# 08_-_QSFP28_2.net
KiCad netlist of a schematic drawn in Altium Designer
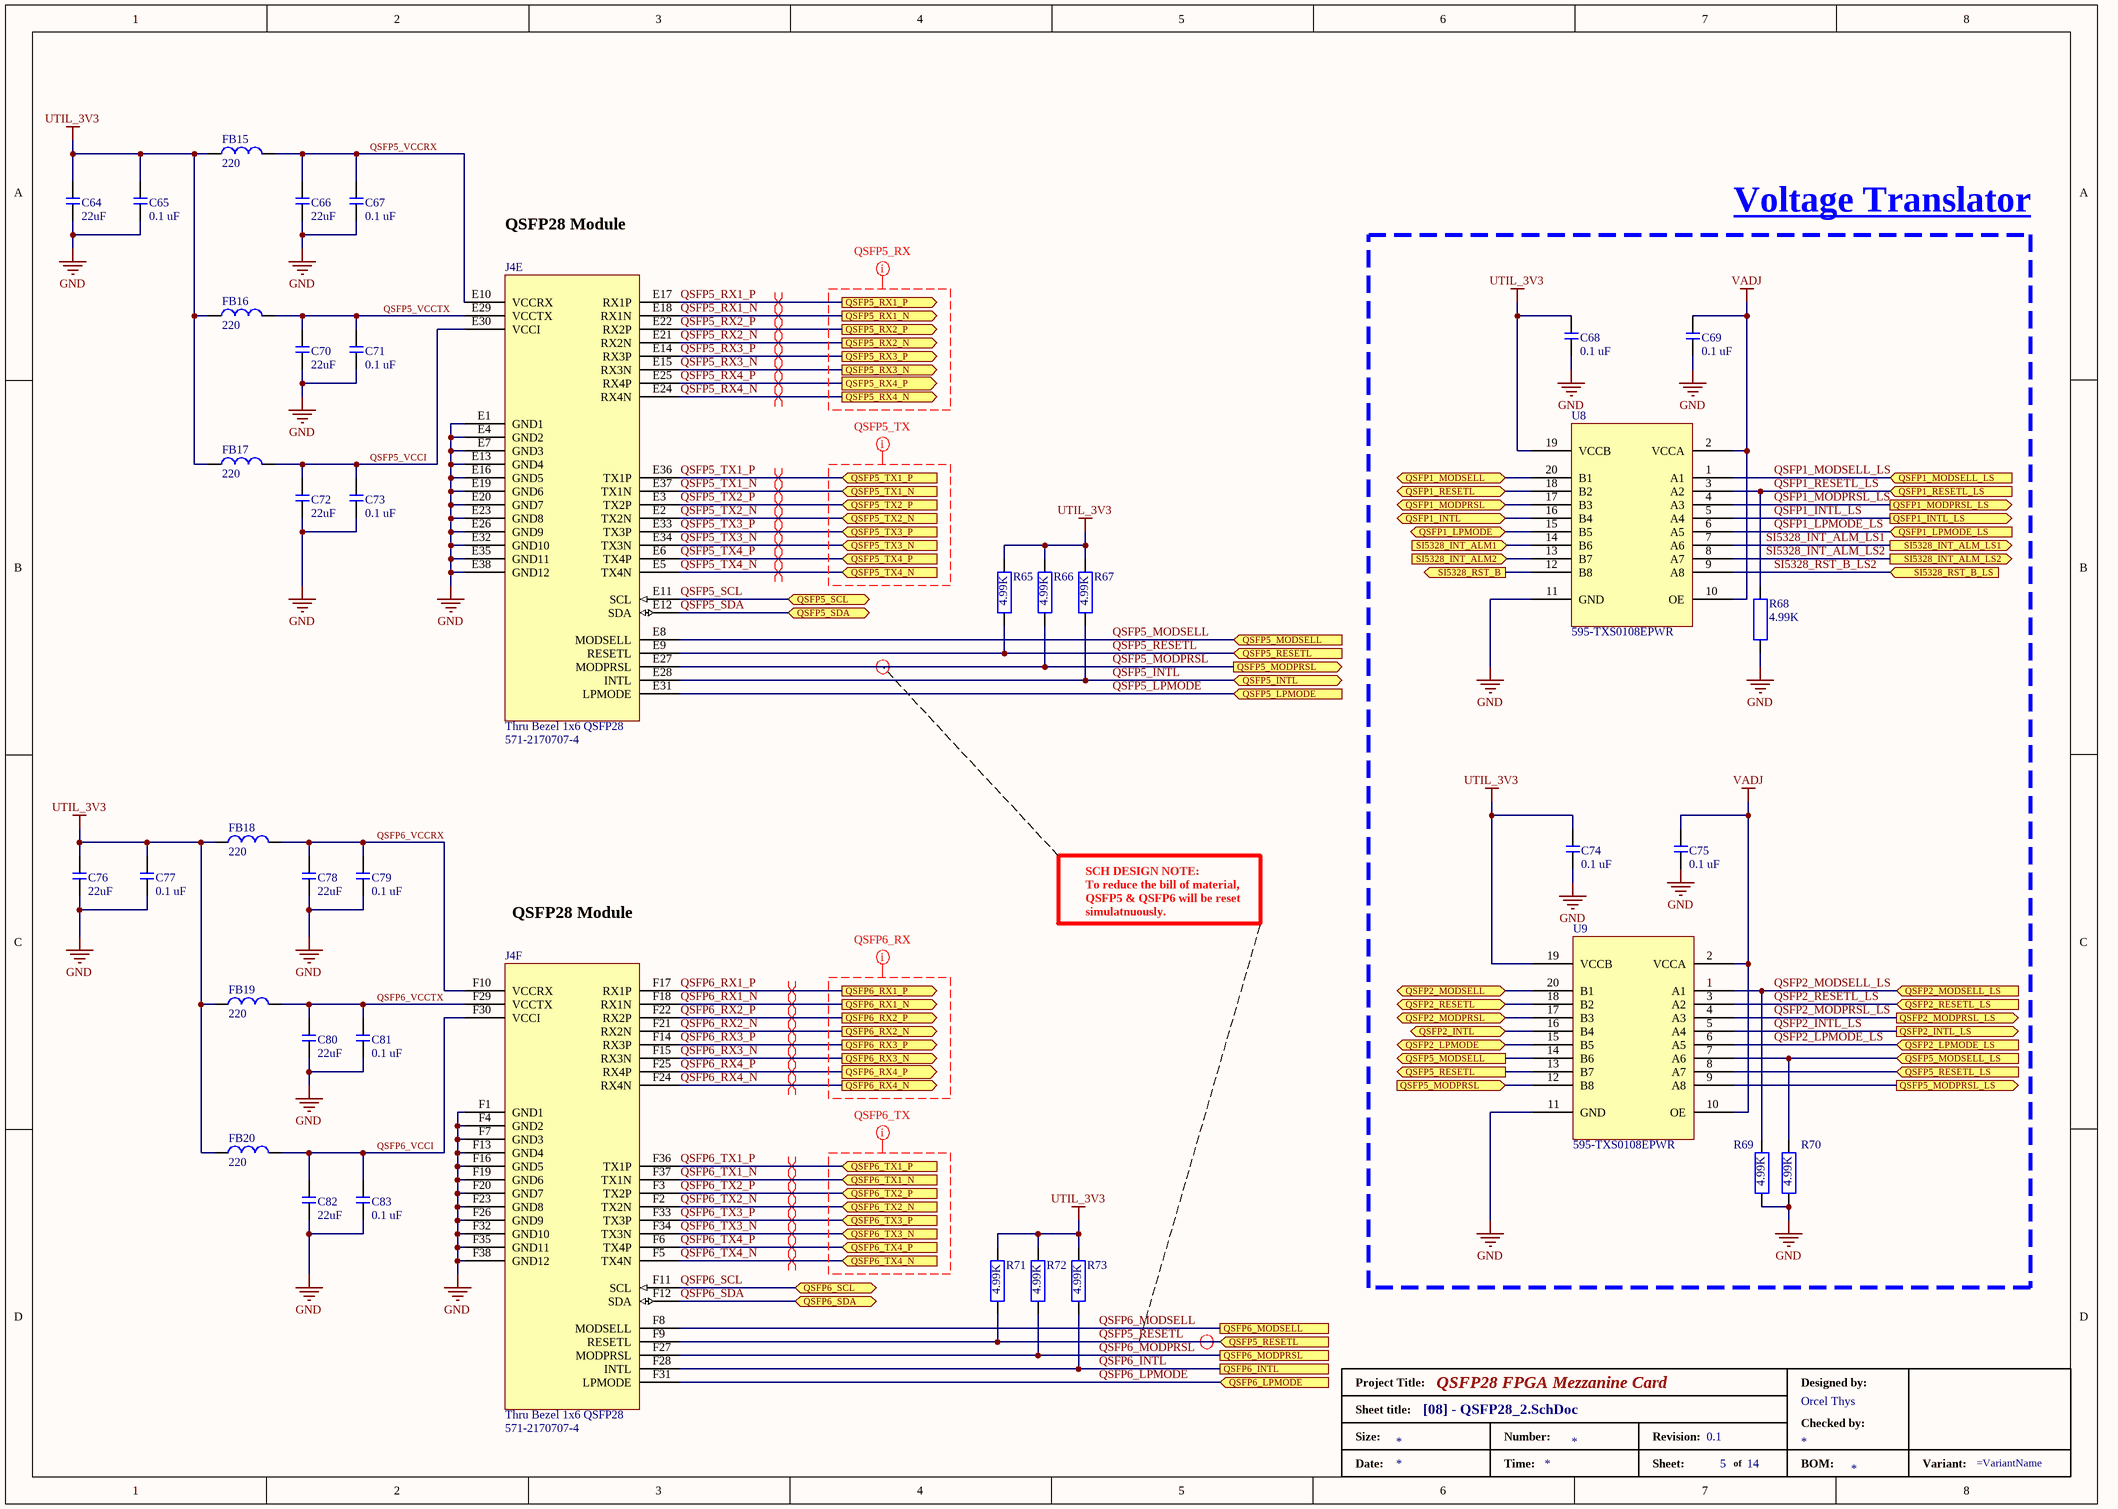
[diagram p0: [08] - QSFP28_2.SchDoc]

(export (version "E")
  (design (tool "Eeschema 10.0.6"))
  (components
    (comp (ref "C64")
      (value "22uF")
      (footprint "C2012")
      (description "Cap Series 0805 22 uF 35 V ±20 % Tolerance X5R SMT Multilayer Ceramic Capacitor")
      (fields
        (field (name "MANUFACTURER") "TDK")
        (field (name "MANUFACTURER PART NUMBER") "C2012X5R1V226M125AC")
      )
      (libsource (lib "QSFP28_FMC_lib") (part "C2012X5R1V226M125AC"))
    )
    (comp (ref "C65")
      (value "0.1 uF")
      (footprint "C0402")
      (description "Cap 0402 0.1 uF 50 V ±10 % Tolerance X7R Surface Mount Multilayer Ceramic Capacitor")
      (fields
        (field (name "MANUFACTURER") "Taiyo Yuden")
        (field (name "MANUFACTURER PART NUMBER") "UMK105B7104KV-FR")
      )
      (libsource (lib "QSFP28_FMC_lib") (part "UMK105B7104KV-FR"))
    )
    (comp (ref "C66")
      (value "22uF")
      (footprint "C2012")
      (description "Cap Series 0805 22 uF 35 V ±20 % Tolerance X5R SMT Multilayer Ceramic Capacitor")
      (fields
        (field (name "MANUFACTURER") "TDK")
        (field (name "MANUFACTURER PART NUMBER") "C2012X5R1V226M125AC")
      )
      (libsource (lib "QSFP28_FMC_lib") (part "C2012X5R1V226M125AC"))
    )
    (comp (ref "C67")
      (value "0.1 uF")
      (footprint "C0402")
      (description "Cap 0402 0.1 uF 50 V ±10 % Tolerance X7R Surface Mount Multilayer Ceramic Capacitor")
      (fields
        (field (name "MANUFACTURER") "Taiyo Yuden")
        (field (name "MANUFACTURER PART NUMBER") "UMK105B7104KV-FR")
      )
      (libsource (lib "QSFP28_FMC_lib") (part "UMK105B7104KV-FR"))
    )
    (comp (ref "C68")
      (value "0.1 uF")
      (footprint "C0402")
      (description "Cap 0402 0.1 uF 50 V ±10 % Tolerance X7R Surface Mount Multilayer Ceramic Capacitor")
      (fields
        (field (name "MANUFACTURER") "Taiyo Yuden")
        (field (name "MANUFACTURER PART NUMBER") "UMK105B7104KV-FR")
      )
      (libsource (lib "QSFP28_FMC_lib") (part "UMK105B7104KV-FR"))
    )
    (comp (ref "C69")
      (value "0.1 uF")
      (footprint "C0402")
      (description "Cap 0402 0.1 uF 50 V ±10 % Tolerance X7R Surface Mount Multilayer Ceramic Capacitor")
      (fields
        (field (name "MANUFACTURER") "Taiyo Yuden")
        (field (name "MANUFACTURER PART NUMBER") "UMK105B7104KV-FR")
      )
      (libsource (lib "QSFP28_FMC_lib") (part "UMK105B7104KV-FR"))
    )
    (comp (ref "C70")
      (value "22uF")
      (footprint "C2012")
      (description "Cap Series 0805 22 uF 35 V ±20 % Tolerance X5R SMT Multilayer Ceramic Capacitor")
      (fields
        (field (name "MANUFACTURER") "TDK")
        (field (name "MANUFACTURER PART NUMBER") "C2012X5R1V226M125AC")
      )
      (libsource (lib "QSFP28_FMC_lib") (part "C2012X5R1V226M125AC"))
    )
    (comp (ref "C71")
      (value "0.1 uF")
      (footprint "C0402")
      (description "Cap 0402 0.1 uF 50 V ±10 % Tolerance X7R Surface Mount Multilayer Ceramic Capacitor")
      (fields
        (field (name "MANUFACTURER") "Taiyo Yuden")
        (field (name "MANUFACTURER PART NUMBER") "UMK105B7104KV-FR")
      )
      (libsource (lib "QSFP28_FMC_lib") (part "UMK105B7104KV-FR"))
    )
    (comp (ref "C72")
      (value "22uF")
      (footprint "C2012")
      (description "Cap Series 0805 22 uF 35 V ±20 % Tolerance X5R SMT Multilayer Ceramic Capacitor")
      (fields
        (field (name "MANUFACTURER") "TDK")
        (field (name "MANUFACTURER PART NUMBER") "C2012X5R1V226M125AC")
      )
      (libsource (lib "QSFP28_FMC_lib") (part "C2012X5R1V226M125AC"))
    )
    (comp (ref "C73")
      (value "0.1 uF")
      (footprint "C0402")
      (description "Cap 0402 0.1 uF 50 V ±10 % Tolerance X7R Surface Mount Multilayer Ceramic Capacitor")
      (fields
        (field (name "MANUFACTURER") "Taiyo Yuden")
        (field (name "MANUFACTURER PART NUMBER") "UMK105B7104KV-FR")
      )
      (libsource (lib "QSFP28_FMC_lib") (part "UMK105B7104KV-FR"))
    )
    (comp (ref "C74")
      (value "0.1 uF")
      (footprint "C0402")
      (description "Cap 0402 0.1 uF 50 V ±10 % Tolerance X7R Surface Mount Multilayer Ceramic Capacitor")
      (fields
        (field (name "MANUFACTURER") "Taiyo Yuden")
        (field (name "MANUFACTURER PART NUMBER") "UMK105B7104KV-FR")
      )
      (libsource (lib "QSFP28_FMC_lib") (part "UMK105B7104KV-FR"))
    )
    (comp (ref "C75")
      (value "0.1 uF")
      (footprint "C0402")
      (description "Cap 0402 0.1 uF 50 V ±10 % Tolerance X7R Surface Mount Multilayer Ceramic Capacitor")
      (fields
        (field (name "MANUFACTURER") "Taiyo Yuden")
        (field (name "MANUFACTURER PART NUMBER") "UMK105B7104KV-FR")
      )
      (libsource (lib "QSFP28_FMC_lib") (part "UMK105B7104KV-FR"))
    )
    (comp (ref "C76")
      (value "22uF")
      (footprint "C2012")
      (description "Cap Series 0805 22 uF 35 V ±20 % Tolerance X5R SMT Multilayer Ceramic Capacitor")
      (fields
        (field (name "MANUFACTURER") "TDK")
        (field (name "MANUFACTURER PART NUMBER") "C2012X5R1V226M125AC")
      )
      (libsource (lib "QSFP28_FMC_lib") (part "C2012X5R1V226M125AC"))
    )
    (comp (ref "C77")
      (value "0.1 uF")
      (footprint "C0402")
      (description "Cap 0402 0.1 uF 50 V ±10 % Tolerance X7R Surface Mount Multilayer Ceramic Capacitor")
      (fields
        (field (name "MANUFACTURER") "Taiyo Yuden")
        (field (name "MANUFACTURER PART NUMBER") "UMK105B7104KV-FR")
      )
      (libsource (lib "QSFP28_FMC_lib") (part "UMK105B7104KV-FR"))
    )
    (comp (ref "C78")
      (value "22uF")
      (footprint "C2012")
      (description "Cap Series 0805 22 uF 35 V ±20 % Tolerance X5R SMT Multilayer Ceramic Capacitor")
      (fields
        (field (name "MANUFACTURER") "TDK")
        (field (name "MANUFACTURER PART NUMBER") "C2012X5R1V226M125AC")
      )
      (libsource (lib "QSFP28_FMC_lib") (part "C2012X5R1V226M125AC"))
    )
    (comp (ref "C79")
      (value "0.1 uF")
      (footprint "C0402")
      (description "Cap 0402 0.1 uF 50 V ±10 % Tolerance X7R Surface Mount Multilayer Ceramic Capacitor")
      (fields
        (field (name "MANUFACTURER") "Taiyo Yuden")
        (field (name "MANUFACTURER PART NUMBER") "UMK105B7104KV-FR")
      )
      (libsource (lib "QSFP28_FMC_lib") (part "UMK105B7104KV-FR"))
    )
    (comp (ref "C80")
      (value "22uF")
      (footprint "C2012")
      (description "Cap Series 0805 22 uF 35 V ±20 % Tolerance X5R SMT Multilayer Ceramic Capacitor")
      (fields
        (field (name "MANUFACTURER") "TDK")
        (field (name "MANUFACTURER PART NUMBER") "C2012X5R1V226M125AC")
      )
      (libsource (lib "QSFP28_FMC_lib") (part "C2012X5R1V226M125AC"))
    )
    (comp (ref "C81")
      (value "0.1 uF")
      (footprint "C0402")
      (description "Cap 0402 0.1 uF 50 V ±10 % Tolerance X7R Surface Mount Multilayer Ceramic Capacitor")
      (fields
        (field (name "MANUFACTURER") "Taiyo Yuden")
        (field (name "MANUFACTURER PART NUMBER") "UMK105B7104KV-FR")
      )
      (libsource (lib "QSFP28_FMC_lib") (part "UMK105B7104KV-FR"))
    )
    (comp (ref "C82")
      (value "22uF")
      (footprint "C2012")
      (description "Cap Series 0805 22 uF 35 V ±20 % Tolerance X5R SMT Multilayer Ceramic Capacitor")
      (fields
        (field (name "MANUFACTURER") "TDK")
        (field (name "MANUFACTURER PART NUMBER") "C2012X5R1V226M125AC")
      )
      (libsource (lib "QSFP28_FMC_lib") (part "C2012X5R1V226M125AC"))
    )
    (comp (ref "C83")
      (value "0.1 uF")
      (footprint "C0402")
      (description "Cap 0402 0.1 uF 50 V ±10 % Tolerance X7R Surface Mount Multilayer Ceramic Capacitor")
      (fields
        (field (name "MANUFACTURER") "Taiyo Yuden")
        (field (name "MANUFACTURER PART NUMBER") "UMK105B7104KV-FR")
      )
      (libsource (lib "QSFP28_FMC_lib") (part "UMK105B7104KV-FR"))
    )
    (comp (ref "FB15")
      (value "220")
      (footprint "BEADC1608X75N")
      (description "0603 220Ω ±25% DCR=0.050Ω 2.2A")
      (fields
        (field (name "MANUFACTURER") "TDK")
        (field (name "MANUFACTURER PART NUMBER") "MPZ1608S221ATA00")
      )
      (libsource (lib "QSFP28_FMC_lib") (part "MPZ1608S221ATA00"))
    )
    (comp (ref "FB16")
      (value "220")
      (footprint "BEADC1608X75N")
      (description "0603 220Ω ±25% DCR=0.050Ω 2.2A")
      (fields
        (field (name "MANUFACTURER") "TDK")
        (field (name "MANUFACTURER PART NUMBER") "MPZ1608S221ATA00")
      )
      (libsource (lib "QSFP28_FMC_lib") (part "MPZ1608S221ATA00"))
    )
    (comp (ref "FB17")
      (value "220")
      (footprint "BEADC1608X75N")
      (description "0603 220Ω ±25% DCR=0.050Ω 2.2A")
      (fields
        (field (name "MANUFACTURER") "TDK")
        (field (name "MANUFACTURER PART NUMBER") "MPZ1608S221ATA00")
      )
      (libsource (lib "QSFP28_FMC_lib") (part "MPZ1608S221ATA00"))
    )
    (comp (ref "FB18")
      (value "220")
      (footprint "BEADC1608X75N")
      (description "0603 220Ω ±25% DCR=0.050Ω 2.2A")
      (fields
        (field (name "MANUFACTURER") "TDK")
        (field (name "MANUFACTURER PART NUMBER") "MPZ1608S221ATA00")
      )
      (libsource (lib "QSFP28_FMC_lib") (part "MPZ1608S221ATA00"))
    )
    (comp (ref "FB19")
      (value "220")
      (footprint "BEADC1608X75N")
      (description "0603 220Ω ±25% DCR=0.050Ω 2.2A")
      (fields
        (field (name "MANUFACTURER") "TDK")
        (field (name "MANUFACTURER PART NUMBER") "MPZ1608S221ATA00")
      )
      (libsource (lib "QSFP28_FMC_lib") (part "MPZ1608S221ATA00"))
    )
    (comp (ref "FB20")
      (value "220")
      (footprint "BEADC1608X75N")
      (description "0603 220Ω ±25% DCR=0.050Ω 2.2A")
      (fields
        (field (name "MANUFACTURER") "TDK")
        (field (name "MANUFACTURER PART NUMBER") "MPZ1608S221ATA00")
      )
      (libsource (lib "QSFP28_FMC_lib") (part "MPZ1608S221ATA00"))
    )
    (comp (ref "J4")
      (value "Thru Bezel 1x6 QSFP28")
      (footprint "TE_2170707-4")
      (description "Cage Assy, 1X6, QSFP28, Spring, Hs")
      (fields
        (field (name "MANUFACTURER") "TE Connectivity AMP")
        (field (name "MANUFACTURER PART NUMBER") "2170707-4")
        (field (name "SUPPLIER PART NUMBER 1") "571-2170707-4")
      )
      (libsource (lib "QSFP28_FMC_lib") (part "2170707-4"))
    )
    (comp (ref "R65")
      (value "4.99K")
      (footprint "R0402")
      (description "RES SMD 4.99K OHM 1% 1/10W 0402")
      (fields
        (field (name "MANUFACTURER") "Panasonic")
        (field (name "MANUFACTURER PART NUMBER") "ERJ-2RKF4991X")
      )
      (libsource (lib "QSFP28_FMC_lib") (part "ERJ-2RKF4991X"))
    )
    (comp (ref "R66")
      (value "4.99K")
      (footprint "R0402")
      (description "RES SMD 4.99K OHM 1% 1/10W 0402")
      (fields
        (field (name "MANUFACTURER") "Panasonic")
        (field (name "MANUFACTURER PART NUMBER") "ERJ-2RKF4991X")
      )
      (libsource (lib "QSFP28_FMC_lib") (part "ERJ-2RKF4991X"))
    )
    (comp (ref "R67")
      (value "4.99K")
      (footprint "R0402")
      (description "RES SMD 4.99K OHM 1% 1/10W 0402")
      (fields
        (field (name "MANUFACTURER") "Panasonic")
        (field (name "MANUFACTURER PART NUMBER") "ERJ-2RKF4991X")
      )
      (libsource (lib "QSFP28_FMC_lib") (part "ERJ-2RKF4991X"))
    )
    (comp (ref "R68")
      (value "4.99K")
      (footprint "R0402")
      (description "RES SMD 4.99K OHM 1% 1/10W 0402")
      (fields
        (field (name "MANUFACTURER") "Panasonic")
        (field (name "MANUFACTURER PART NUMBER") "ERJ-2RKF4991X")
      )
      (libsource (lib "QSFP28_FMC_lib") (part "ERJ-2RKF4991X"))
    )
    (comp (ref "R69")
      (value "4.99K")
      (footprint "R0402")
      (description "RES SMD 4.99K OHM 1% 1/10W 0402")
      (fields
        (field (name "MANUFACTURER") "Panasonic")
        (field (name "MANUFACTURER PART NUMBER") "ERJ-2RKF4991X")
      )
      (libsource (lib "QSFP28_FMC_lib") (part "ERJ-2RKF4991X"))
    )
    (comp (ref "R70")
      (value "4.99K")
      (footprint "R0402")
      (description "RES SMD 4.99K OHM 1% 1/10W 0402")
      (fields
        (field (name "MANUFACTURER") "Panasonic")
        (field (name "MANUFACTURER PART NUMBER") "ERJ-2RKF4991X")
      )
      (libsource (lib "QSFP28_FMC_lib") (part "ERJ-2RKF4991X"))
    )
    (comp (ref "R71")
      (value "4.99K")
      (footprint "R0402")
      (description "RES SMD 4.99K OHM 1% 1/10W 0402")
      (fields
        (field (name "MANUFACTURER") "Panasonic")
        (field (name "MANUFACTURER PART NUMBER") "ERJ-2RKF4991X")
      )
      (libsource (lib "QSFP28_FMC_lib") (part "ERJ-2RKF4991X"))
    )
    (comp (ref "R72")
      (value "4.99K")
      (footprint "R0402")
      (description "RES SMD 4.99K OHM 1% 1/10W 0402")
      (fields
        (field (name "MANUFACTURER") "Panasonic")
        (field (name "MANUFACTURER PART NUMBER") "ERJ-2RKF4991X")
      )
      (libsource (lib "QSFP28_FMC_lib") (part "ERJ-2RKF4991X"))
    )
    (comp (ref "R73")
      (value "4.99K")
      (footprint "R0402")
      (description "RES SMD 4.99K OHM 1% 1/10W 0402")
      (fields
        (field (name "MANUFACTURER") "Panasonic")
        (field (name "MANUFACTURER PART NUMBER") "ERJ-2RKF4991X")
      )
      (libsource (lib "QSFP28_FMC_lib") (part "ERJ-2RKF4991X"))
    )
    (comp (ref "U8")
      (value "8-bit voltage translator")
      (footprint "SOP_65P640X120-20N")
      (description "IC 8BIT NON-INV TRANSLTR 20TSSOP")
      (fields
        (field (name "MANUFACTURER") "Texas Instruments")
        (field (name "MANUFACTURER PART NUMBER") "TXS0108EPWR")
        (field (name "SUPPLIER PART NUMBER 1") "595-TXS0108EPWR")
      )
      (libsource (lib "FmcLib") (part "TXS0108EPWR"))
    )
    (comp (ref "U9")
      (value "8-bit voltage translator")
      (footprint "SOP_65P640X120-20N")
      (description "IC 8BIT NON-INV TRANSLTR 20TSSOP")
      (fields
        (field (name "MANUFACTURER") "Texas Instruments")
        (field (name "MANUFACTURER PART NUMBER") "TXS0108EPWR")
        (field (name "SUPPLIER PART NUMBER 1") "595-TXS0108EPWR")
      )
      (libsource (lib "FmcLib") (part "TXS0108EPWR"))
    )
  )
  (nets
    (net (code "1") (name "/QSFP1_INTL") (class "Default")
      (node (ref "U8") (pin "16") (pinfunction "B4_16") (pintype "passive"))
    )
    (net (code "2") (name "/QSFP1_INTL_LS") (class "Default")
      (node (ref "U8") (pin "5") (pinfunction "A4_5") (pintype "passive"))
    )
    (net (code "3") (name "/QSFP1_LPMODE") (class "Default")
      (node (ref "U8") (pin "15") (pinfunction "B5_15") (pintype "passive"))
    )
    (net (code "4") (name "/QSFP1_LPMODE_LS") (class "Default")
      (node (ref "U8") (pin "6") (pinfunction "A5_6") (pintype "passive"))
    )
    (net (code "5") (name "/QSFP1_MODPRSL") (class "Default")
      (node (ref "U8") (pin "17") (pinfunction "B3_17") (pintype "passive"))
    )
    (net (code "6") (name "/QSFP1_MODPRSL_LS") (class "Default")
      (node (ref "U8") (pin "4") (pinfunction "A3_4") (pintype "passive"))
    )
    (net (code "7") (name "/QSFP1_MODSELL") (class "Default")
      (node (ref "U8") (pin "20") (pinfunction "B1_20") (pintype "passive"))
    )
    (net (code "8") (name "/QSFP1_MODSELL_LS") (class "Default")
      (node (ref "U8") (pin "1") (pinfunction "A1_1") (pintype "passive"))
    )
    (net (code "9") (name "/QSFP1_RESETL") (class "Default")
      (node (ref "U8") (pin "18") (pinfunction "B2_18") (pintype "passive"))
    )
    (net (code "10") (name "/QSFP1_RESETL_LS") (class "Default")
      (node (ref "R68") (pin "2") (pintype "passive"))
      (node (ref "U8") (pin "3") (pinfunction "A2_3") (pintype "passive"))
    )
    (net (code "11") (name "/QSFP2_INTL") (class "Default")
      (node (ref "U9") (pin "16") (pinfunction "B4_16") (pintype "passive"))
    )
    (net (code "12") (name "/QSFP2_INTL_LS") (class "Default")
      (node (ref "U9") (pin "5") (pinfunction "A4_5") (pintype "passive"))
    )
    (net (code "13") (name "/QSFP2_LPMODE") (class "Default")
      (node (ref "U9") (pin "15") (pinfunction "B5_15") (pintype "passive"))
    )
    (net (code "14") (name "/QSFP2_LPMODE_LS") (class "Default")
      (node (ref "U9") (pin "6") (pinfunction "A5_6") (pintype "passive"))
    )
    (net (code "15") (name "/QSFP2_MODPRSL") (class "Default")
      (node (ref "U9") (pin "17") (pinfunction "B3_17") (pintype "passive"))
    )
    (net (code "16") (name "/QSFP2_MODPRSL_LS") (class "Default")
      (node (ref "U9") (pin "4") (pinfunction "A3_4") (pintype "passive"))
    )
    (net (code "17") (name "/QSFP2_MODSELL") (class "Default")
      (node (ref "U9") (pin "20") (pinfunction "B1_20") (pintype "passive"))
    )
    (net (code "18") (name "/QSFP2_MODSELL_LS") (class "Default")
      (node (ref "R69") (pin "2") (pintype "passive"))
      (node (ref "U9") (pin "1") (pinfunction "A1_1") (pintype "passive"))
    )
    (net (code "19") (name "/QSFP2_RESETL") (class "Default")
      (node (ref "U9") (pin "18") (pinfunction "B2_18") (pintype "passive"))
    )
    (net (code "20") (name "/QSFP2_RESETL_LS") (class "Default")
      (node (ref "U9") (pin "3") (pinfunction "A2_3") (pintype "passive"))
    )
    (net (code "21") (name "/QSFP5_INTL") (class "Default")
      (node (ref "J4") (pin "E28") (pinfunction "INTL_E28") (pintype "passive"))
      (node (ref "R67") (pin "1") (pintype "passive"))
    )
    (net (code "22") (name "/QSFP5_LPMODE") (class "Default")
      (node (ref "J4") (pin "E31") (pinfunction "LPMODE_E31") (pintype "passive"))
    )
    (net (code "23") (name "/QSFP5_MODPRSL") (class "Default")
      (node (ref "J4") (pin "E27") (pinfunction "MODPRSL_E27") (pintype "passive"))
      (node (ref "R66") (pin "1") (pintype "passive"))
      (node (ref "U9") (pin "12") (pinfunction "B8_12") (pintype "passive"))
    )
    (net (code "24") (name "/QSFP5_MODPRSL_LS") (class "Default")
      (node (ref "U9") (pin "9") (pinfunction "A8_9") (pintype "passive"))
    )
    (net (code "25") (name "/QSFP5_MODSELL") (class "Default")
      (node (ref "J4") (pin "E8") (pinfunction "MODSELL_E8") (pintype "passive"))
      (node (ref "U9") (pin "14") (pinfunction "B6_14") (pintype "passive"))
    )
    (net (code "26") (name "/QSFP5_MODSELL_LS") (class "Default")
      (node (ref "R70") (pin "2") (pintype "passive"))
      (node (ref "U9") (pin "7") (pinfunction "A6_7") (pintype "passive"))
    )
    (net (code "27") (name "/QSFP5_RESETL") (class "Default")
      (node (ref "J4") (pin "E9") (pinfunction "RESETL_E9") (pintype "passive"))
      (node (ref "J4") (pin "F9") (pinfunction "RESETL_F9") (pintype "passive"))
      (node (ref "R65") (pin "1") (pintype "passive"))
      (node (ref "R71") (pin "1") (pintype "passive"))
      (node (ref "U9") (pin "13") (pinfunction "B7_13") (pintype "passive"))
    )
    (net (code "28") (name "/QSFP5_RESETL_LS") (class "Default")
      (node (ref "U9") (pin "8") (pinfunction "A7_8") (pintype "passive"))
    )
    (net (code "29") (name "/QSFP5_RX1_N") (class "Default")
      (node (ref "J4") (pin "E18") (pinfunction "RX1N_E18") (pintype "passive"))
    )
    (net (code "30") (name "/QSFP5_RX1_P") (class "Default")
      (node (ref "J4") (pin "E17") (pinfunction "RX1P_E17") (pintype "passive"))
    )
    (net (code "31") (name "/QSFP5_RX2_N") (class "Default")
      (node (ref "J4") (pin "E21") (pinfunction "RX2N_E21") (pintype "passive"))
    )
    (net (code "32") (name "/QSFP5_RX2_P") (class "Default")
      (node (ref "J4") (pin "E22") (pinfunction "RX2P_E22") (pintype "passive"))
    )
    (net (code "33") (name "/QSFP5_RX3_N") (class "Default")
      (node (ref "J4") (pin "E15") (pinfunction "RX3N_E15") (pintype "passive"))
    )
    (net (code "34") (name "/QSFP5_RX3_P") (class "Default")
      (node (ref "J4") (pin "E14") (pinfunction "RX3P_E14") (pintype "passive"))
    )
    (net (code "35") (name "/QSFP5_RX4_N") (class "Default")
      (node (ref "J4") (pin "E24") (pinfunction "RX4N_E24") (pintype "passive"))
    )
    (net (code "36") (name "/QSFP5_RX4_P") (class "Default")
      (node (ref "J4") (pin "E25") (pinfunction "RX4P_E25") (pintype "passive"))
    )
    (net (code "37") (name "/QSFP5_SCL") (class "Default")
      (node (ref "J4") (pin "E11") (pinfunction "SCL_E11") (pintype "input"))
    )
    (net (code "38") (name "/QSFP5_SDA") (class "Default")
      (node (ref "J4") (pin "E12") (pinfunction "SDA_E12") (pintype "bidirectional"))
    )
    (net (code "39") (name "/QSFP5_TX1_N") (class "Default")
      (node (ref "J4") (pin "E37") (pinfunction "TX1N_E37") (pintype "passive"))
    )
    (net (code "40") (name "/QSFP5_TX1_P") (class "Default")
      (node (ref "J4") (pin "E36") (pinfunction "TX1P_E36") (pintype "passive"))
    )
    (net (code "41") (name "/QSFP5_TX2_N") (class "Default")
      (node (ref "J4") (pin "E2") (pinfunction "TX2N_E2") (pintype "passive"))
    )
    (net (code "42") (name "/QSFP5_TX2_P") (class "Default")
      (node (ref "J4") (pin "E3") (pinfunction "TX2P_E3") (pintype "passive"))
    )
    (net (code "43") (name "/QSFP5_TX3_N") (class "Default")
      (node (ref "J4") (pin "E34") (pinfunction "TX3N_E34") (pintype "passive"))
    )
    (net (code "44") (name "/QSFP5_TX3_P") (class "Default")
      (node (ref "J4") (pin "E33") (pinfunction "TX3P_E33") (pintype "passive"))
    )
    (net (code "45") (name "/QSFP5_TX4_N") (class "Default")
      (node (ref "J4") (pin "E5") (pinfunction "TX4N_E5") (pintype "passive"))
    )
    (net (code "46") (name "/QSFP5_TX4_P") (class "Default")
      (node (ref "J4") (pin "E6") (pinfunction "TX4P_E6") (pintype "passive"))
    )
    (net (code "47") (name "/QSFP5_VCCI") (class "Default")
      (node (ref "C72") (pin "2") (pinfunction "2_2") (pintype "passive"))
      (node (ref "C73") (pin "2") (pinfunction "2_2") (pintype "passive"))
      (node (ref "FB17") (pin "2") (pintype "passive"))
      (node (ref "J4") (pin "E30") (pinfunction "VCCI_E30") (pintype "power_in"))
    )
    (net (code "48") (name "/QSFP5_VCCRX") (class "Default")
      (node (ref "C66") (pin "2") (pinfunction "2_2") (pintype "passive"))
      (node (ref "C67") (pin "2") (pinfunction "2_2") (pintype "passive"))
      (node (ref "FB15") (pin "2") (pintype "passive"))
      (node (ref "J4") (pin "E10") (pinfunction "VCCRX_E10") (pintype "power_in"))
    )
    (net (code "49") (name "/QSFP5_VCCTX") (class "Default")
      (node (ref "C70") (pin "2") (pinfunction "2_2") (pintype "passive"))
      (node (ref "C71") (pin "2") (pinfunction "2_2") (pintype "passive"))
      (node (ref "FB16") (pin "2") (pintype "passive"))
      (node (ref "J4") (pin "E29") (pinfunction "VCCTX_E29") (pintype "power_in"))
    )
    (net (code "50") (name "/QSFP6_INTL") (class "Default")
      (node (ref "J4") (pin "F28") (pinfunction "INTL_F28") (pintype "passive"))
      (node (ref "R73") (pin "1") (pintype "passive"))
    )
    (net (code "51") (name "/QSFP6_LPMODE") (class "Default")
      (node (ref "J4") (pin "F31") (pinfunction "LPMODE_F31") (pintype "passive"))
    )
    (net (code "52") (name "/QSFP6_MODPRSL") (class "Default")
      (node (ref "J4") (pin "F27") (pinfunction "MODPRSL_F27") (pintype "passive"))
      (node (ref "R72") (pin "1") (pintype "passive"))
    )
    (net (code "53") (name "/QSFP6_MODSELL") (class "Default")
      (node (ref "J4") (pin "F8") (pinfunction "MODSELL_F8") (pintype "passive"))
    )
    (net (code "54") (name "/QSFP6_RX1_N") (class "Default")
      (node (ref "J4") (pin "F18") (pinfunction "RX1N_F18") (pintype "passive"))
    )
    (net (code "55") (name "/QSFP6_RX1_P") (class "Default")
      (node (ref "J4") (pin "F17") (pinfunction "RX1P_F17") (pintype "passive"))
    )
    (net (code "56") (name "/QSFP6_RX2_N") (class "Default")
      (node (ref "J4") (pin "F21") (pinfunction "RX2N_F21") (pintype "passive"))
    )
    (net (code "57") (name "/QSFP6_RX2_P") (class "Default")
      (node (ref "J4") (pin "F22") (pinfunction "RX2P_F22") (pintype "passive"))
    )
    (net (code "58") (name "/QSFP6_RX3_N") (class "Default")
      (node (ref "J4") (pin "F15") (pinfunction "RX3N_F15") (pintype "passive"))
    )
    (net (code "59") (name "/QSFP6_RX3_P") (class "Default")
      (node (ref "J4") (pin "F14") (pinfunction "RX3P_F14") (pintype "passive"))
    )
    (net (code "60") (name "/QSFP6_RX4_N") (class "Default")
      (node (ref "J4") (pin "F24") (pinfunction "RX4N_F24") (pintype "passive"))
    )
    (net (code "61") (name "/QSFP6_RX4_P") (class "Default")
      (node (ref "J4") (pin "F25") (pinfunction "RX4P_F25") (pintype "passive"))
    )
    (net (code "62") (name "/QSFP6_SCL") (class "Default")
      (node (ref "J4") (pin "F11") (pinfunction "SCL_F11") (pintype "input"))
    )
    (net (code "63") (name "/QSFP6_SDA") (class "Default")
      (node (ref "J4") (pin "F12") (pinfunction "SDA_F12") (pintype "bidirectional"))
    )
    (net (code "64") (name "/QSFP6_TX1_N") (class "Default")
      (node (ref "J4") (pin "F37") (pinfunction "TX1N_F37") (pintype "passive"))
    )
    (net (code "65") (name "/QSFP6_TX1_P") (class "Default")
      (node (ref "J4") (pin "F36") (pinfunction "TX1P_F36") (pintype "passive"))
    )
    (net (code "66") (name "/QSFP6_TX2_N") (class "Default")
      (node (ref "J4") (pin "F2") (pinfunction "TX2N_F2") (pintype "passive"))
    )
    (net (code "67") (name "/QSFP6_TX2_P") (class "Default")
      (node (ref "J4") (pin "F3") (pinfunction "TX2P_F3") (pintype "passive"))
    )
    (net (code "68") (name "/QSFP6_TX3_N") (class "Default")
      (node (ref "J4") (pin "F34") (pinfunction "TX3N_F34") (pintype "passive"))
    )
    (net (code "69") (name "/QSFP6_TX3_P") (class "Default")
      (node (ref "J4") (pin "F33") (pinfunction "TX3P_F33") (pintype "passive"))
    )
    (net (code "70") (name "/QSFP6_TX4_N") (class "Default")
      (node (ref "J4") (pin "F5") (pinfunction "TX4N_F5") (pintype "passive"))
    )
    (net (code "71") (name "/QSFP6_TX4_P") (class "Default")
      (node (ref "J4") (pin "F6") (pinfunction "TX4P_F6") (pintype "passive"))
    )
    (net (code "72") (name "/QSFP6_VCCI") (class "Default")
      (node (ref "C82") (pin "2") (pinfunction "2_2") (pintype "passive"))
      (node (ref "C83") (pin "2") (pinfunction "2_2") (pintype "passive"))
      (node (ref "FB20") (pin "2") (pintype "passive"))
      (node (ref "J4") (pin "F30") (pinfunction "VCCI_F30") (pintype "power_in"))
    )
    (net (code "73") (name "/QSFP6_VCCRX") (class "Default")
      (node (ref "C78") (pin "2") (pinfunction "2_2") (pintype "passive"))
      (node (ref "C79") (pin "2") (pinfunction "2_2") (pintype "passive"))
      (node (ref "FB18") (pin "2") (pintype "passive"))
      (node (ref "J4") (pin "F10") (pinfunction "VCCRX_F10") (pintype "power_in"))
    )
    (net (code "74") (name "/QSFP6_VCCTX") (class "Default")
      (node (ref "C80") (pin "2") (pinfunction "2_2") (pintype "passive"))
      (node (ref "C81") (pin "2") (pinfunction "2_2") (pintype "passive"))
      (node (ref "FB19") (pin "2") (pintype "passive"))
      (node (ref "J4") (pin "F29") (pinfunction "VCCTX_F29") (pintype "power_in"))
    )
    (net (code "75") (name "/SI5328_INT_ALM1") (class "Default")
      (node (ref "U8") (pin "14") (pinfunction "B6_14") (pintype "passive"))
    )
    (net (code "76") (name "/SI5328_INT_ALM2") (class "Default")
      (node (ref "U8") (pin "13") (pinfunction "B7_13") (pintype "passive"))
    )
    (net (code "77") (name "/SI5328_INT_ALM_LS1") (class "Default")
      (node (ref "U8") (pin "7") (pinfunction "A6_7") (pintype "passive"))
    )
    (net (code "78") (name "/SI5328_INT_ALM_LS2") (class "Default")
      (node (ref "U8") (pin "8") (pinfunction "A7_8") (pintype "passive"))
    )
    (net (code "79") (name "/SI5328_RST_B") (class "Default")
      (node (ref "U8") (pin "12") (pinfunction "B8_12") (pintype "passive"))
    )
    (net (code "80") (name "/SI5328_RST_B_LS2") (class "Default")
      (node (ref "U8") (pin "9") (pinfunction "A8_9") (pintype "passive"))
    )
    (net (code "81") (name "GND") (class "Default")
      (node (ref "C64") (pin "1") (pinfunction "1_1") (pintype "passive"))
      (node (ref "C65") (pin "1") (pinfunction "1_1") (pintype "passive"))
      (node (ref "C66") (pin "1") (pinfunction "1_1") (pintype "passive"))
      (node (ref "C67") (pin "1") (pinfunction "1_1") (pintype "passive"))
      (node (ref "C68") (pin "2") (pinfunction "2_2") (pintype "passive"))
      (node (ref "C69") (pin "1") (pinfunction "1_1") (pintype "passive"))
      (node (ref "C70") (pin "1") (pinfunction "1_1") (pintype "passive"))
      (node (ref "C71") (pin "1") (pinfunction "1_1") (pintype "passive"))
      (node (ref "C72") (pin "1") (pinfunction "1_1") (pintype "passive"))
      (node (ref "C73") (pin "1") (pinfunction "1_1") (pintype "passive"))
      (node (ref "C74") (pin "1") (pinfunction "1_1") (pintype "passive"))
      (node (ref "C75") (pin "1") (pinfunction "1_1") (pintype "passive"))
      (node (ref "C76") (pin "1") (pinfunction "1_1") (pintype "passive"))
      (node (ref "C77") (pin "1") (pinfunction "1_1") (pintype "passive"))
      (node (ref "C78") (pin "1") (pinfunction "1_1") (pintype "passive"))
      (node (ref "C79") (pin "1") (pinfunction "1_1") (pintype "passive"))
      (node (ref "C80") (pin "1") (pinfunction "1_1") (pintype "passive"))
      (node (ref "C81") (pin "1") (pinfunction "1_1") (pintype "passive"))
      (node (ref "C82") (pin "1") (pinfunction "1_1") (pintype "passive"))
      (node (ref "C83") (pin "1") (pinfunction "1_1") (pintype "passive"))
      (node (ref "J4") (pin "E1") (pinfunction "GND1_E1") (pintype "power_in"))
      (node (ref "J4") (pin "E13") (pinfunction "GND4_E13") (pintype "power_in"))
      (node (ref "J4") (pin "E16") (pinfunction "GND5_E16") (pintype "power_in"))
      (node (ref "J4") (pin "E19") (pinfunction "GND6_E19") (pintype "power_in"))
      (node (ref "J4") (pin "E20") (pinfunction "GND7_E20") (pintype "power_in"))
      (node (ref "J4") (pin "E23") (pinfunction "GND8_E23") (pintype "power_in"))
      (node (ref "J4") (pin "E26") (pinfunction "GND9_E26") (pintype "power_in"))
      (node (ref "J4") (pin "E32") (pinfunction "GND10_E32") (pintype "power_in"))
      (node (ref "J4") (pin "E35") (pinfunction "GND11_E35") (pintype "power_in"))
      (node (ref "J4") (pin "E38") (pinfunction "GND12_E38") (pintype "power_in"))
      (node (ref "J4") (pin "E4") (pinfunction "GND2_E4") (pintype "power_in"))
      (node (ref "J4") (pin "E7") (pinfunction "GND3_E7") (pintype "power_in"))
      (node (ref "J4") (pin "F1") (pinfunction "GND1_F1") (pintype "power_in"))
      (node (ref "J4") (pin "F13") (pinfunction "GND4_F13") (pintype "power_in"))
      (node (ref "J4") (pin "F16") (pinfunction "GND5_F16") (pintype "power_in"))
      (node (ref "J4") (pin "F19") (pinfunction "GND6_F19") (pintype "power_in"))
      (node (ref "J4") (pin "F20") (pinfunction "GND7_F20") (pintype "power_in"))
      (node (ref "J4") (pin "F23") (pinfunction "GND8_F23") (pintype "power_in"))
      (node (ref "J4") (pin "F26") (pinfunction "GND9_F26") (pintype "power_in"))
      (node (ref "J4") (pin "F32") (pinfunction "GND10_F32") (pintype "power_in"))
      (node (ref "J4") (pin "F35") (pinfunction "GND11_F35") (pintype "power_in"))
      (node (ref "J4") (pin "F38") (pinfunction "GND12_F38") (pintype "power_in"))
      (node (ref "J4") (pin "F4") (pinfunction "GND2_F4") (pintype "power_in"))
      (node (ref "J4") (pin "F7") (pinfunction "GND3_F7") (pintype "power_in"))
      (node (ref "R68") (pin "1") (pintype "passive"))
      (node (ref "R69") (pin "1") (pintype "passive"))
      (node (ref "R70") (pin "1") (pintype "passive"))
      (node (ref "U8") (pin "11") (pinfunction "GND_11") (pintype "passive"))
      (node (ref "U9") (pin "11") (pinfunction "GND_11") (pintype "passive"))
    )
    (net (code "82") (name "UTIL_3V3") (class "Default")
      (node (ref "C64") (pin "2") (pinfunction "2_2") (pintype "passive"))
      (node (ref "C65") (pin "2") (pinfunction "2_2") (pintype "passive"))
      (node (ref "C68") (pin "1") (pinfunction "1_1") (pintype "passive"))
      (node (ref "C74") (pin "2") (pinfunction "2_2") (pintype "passive"))
      (node (ref "C76") (pin "2") (pinfunction "2_2") (pintype "passive"))
      (node (ref "C77") (pin "2") (pinfunction "2_2") (pintype "passive"))
      (node (ref "FB15") (pin "1") (pintype "passive"))
      (node (ref "FB16") (pin "1") (pintype "passive"))
      (node (ref "FB17") (pin "1") (pintype "passive"))
      (node (ref "FB18") (pin "1") (pintype "passive"))
      (node (ref "FB19") (pin "1") (pintype "passive"))
      (node (ref "FB20") (pin "1") (pintype "passive"))
      (node (ref "R65") (pin "2") (pintype "passive"))
      (node (ref "R66") (pin "2") (pintype "passive"))
      (node (ref "R67") (pin "2") (pintype "passive"))
      (node (ref "R71") (pin "2") (pintype "passive"))
      (node (ref "R72") (pin "2") (pintype "passive"))
      (node (ref "R73") (pin "2") (pintype "passive"))
      (node (ref "U8") (pin "19") (pinfunction "VCCB_19") (pintype "passive"))
      (node (ref "U9") (pin "19") (pinfunction "VCCB_19") (pintype "passive"))
    )
    (net (code "83") (name "VADJ") (class "Default")
      (node (ref "C69") (pin "2") (pinfunction "2_2") (pintype "passive"))
      (node (ref "C75") (pin "2") (pinfunction "2_2") (pintype "passive"))
      (node (ref "U8") (pin "10") (pinfunction "OE_10") (pintype "passive"))
      (node (ref "U8") (pin "2") (pinfunction "VCCA_2") (pintype "passive"))
      (node (ref "U9") (pin "10") (pinfunction "OE_10") (pintype "passive"))
      (node (ref "U9") (pin "2") (pinfunction "VCCA_2") (pintype "passive"))
    )
  )
)
